# MCU_CORE.net
KiCad netlist of a schematic drawn in Altium Designer
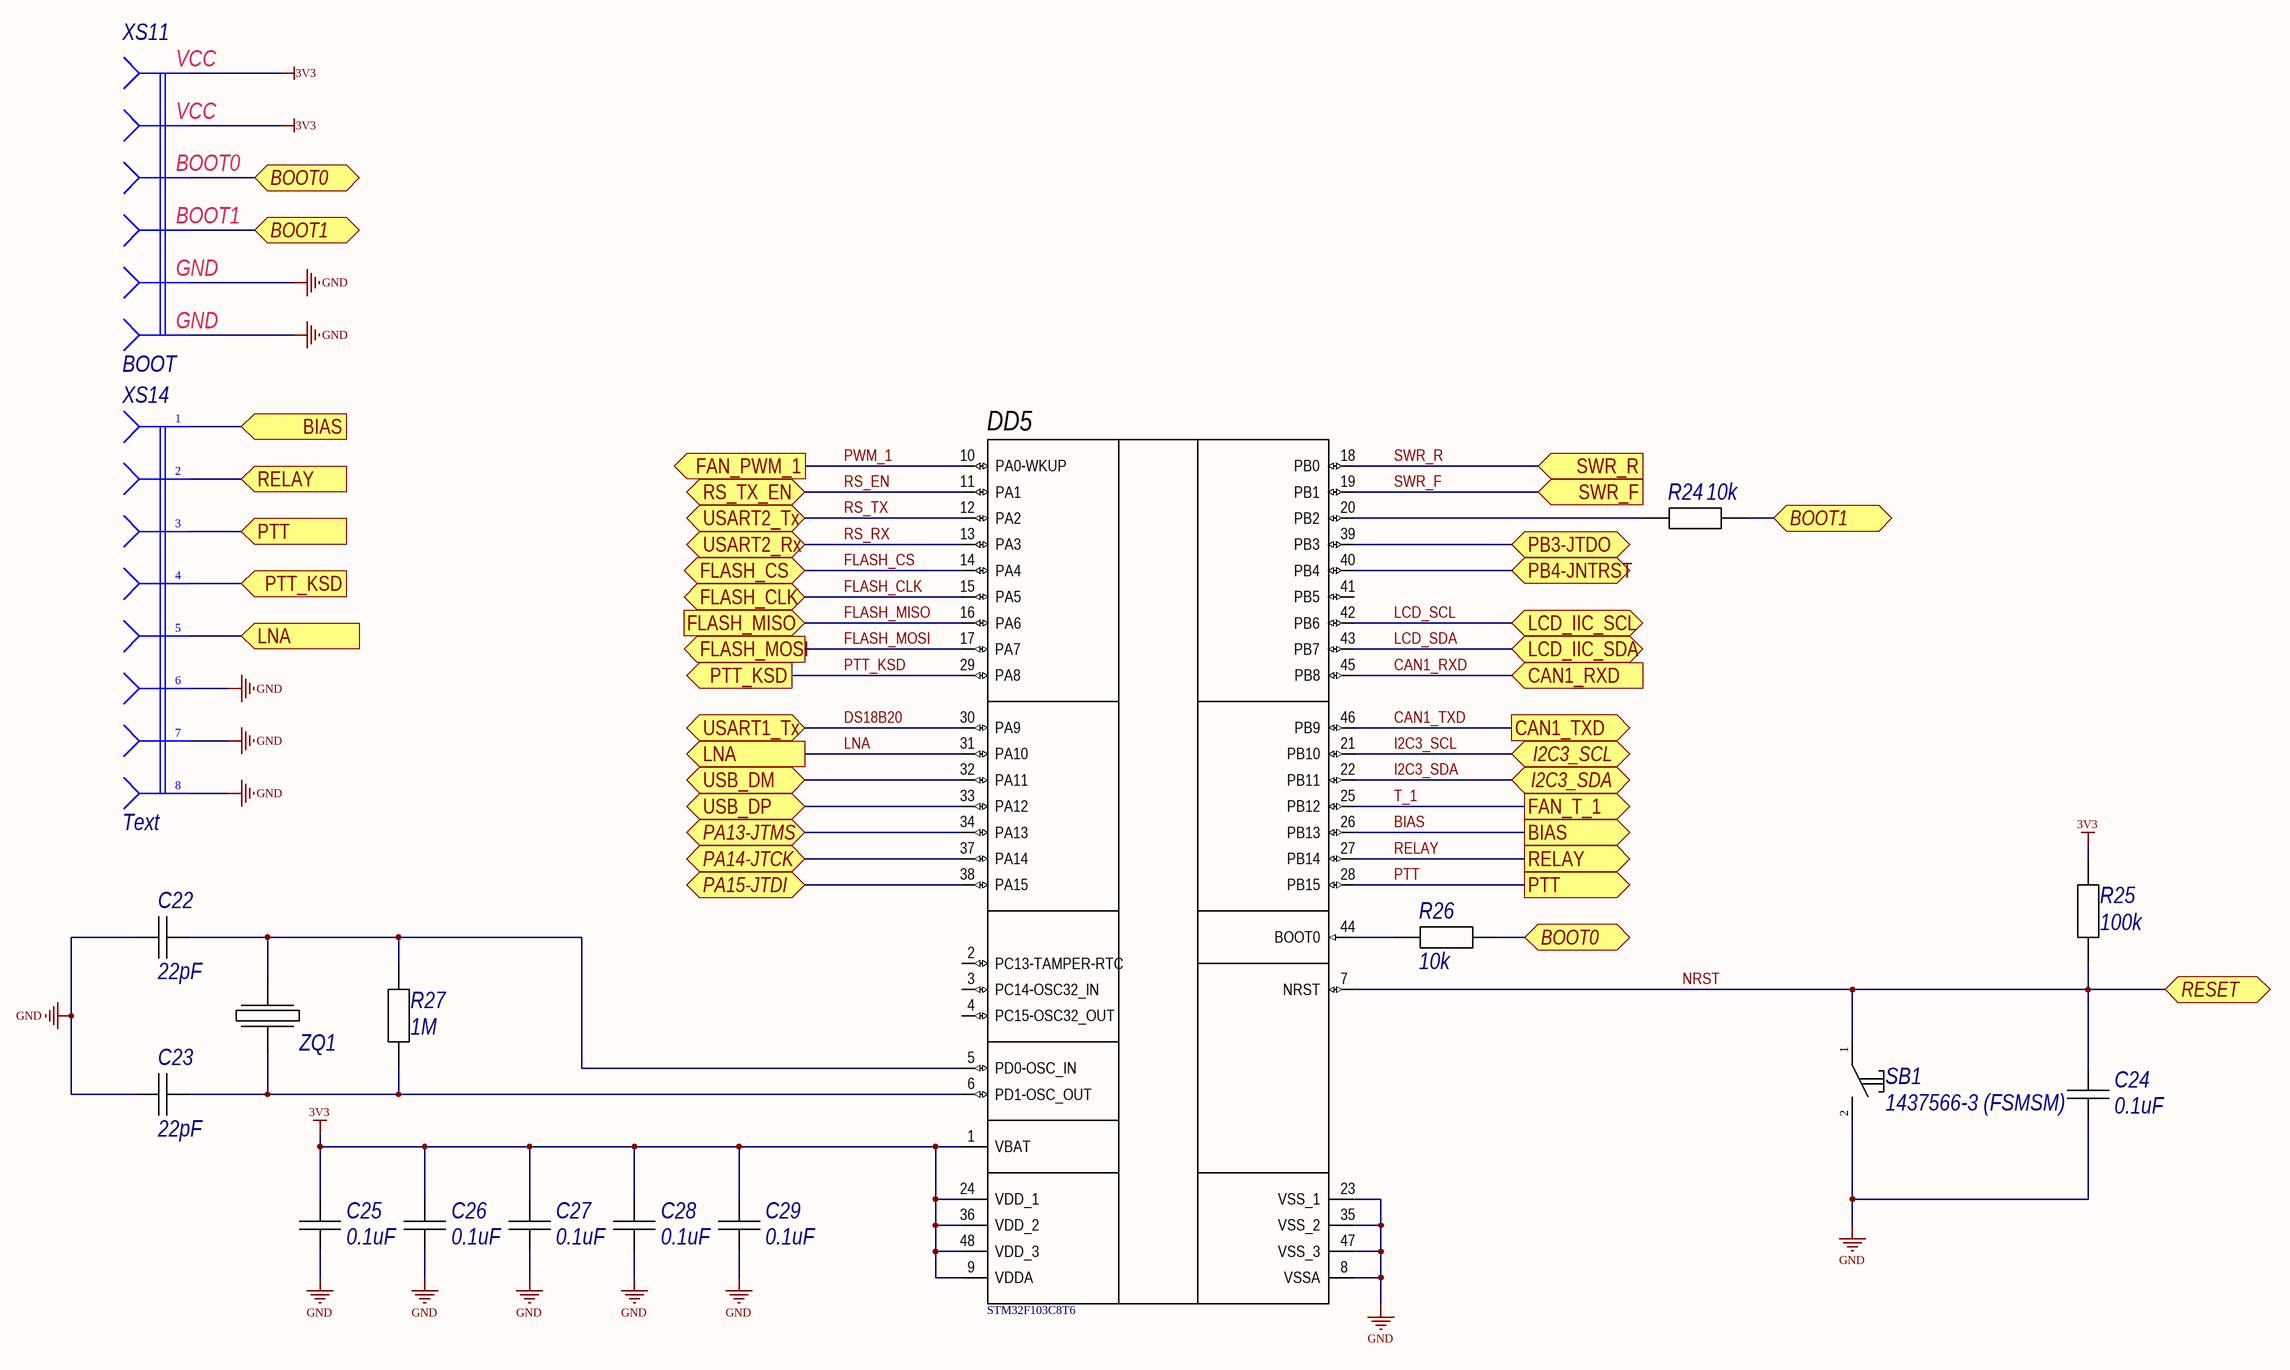
[diagram p0: MCU_CORE.SchDoc]

(export (version "E")
  (design (tool "Eeschema 10.0.6"))
  (components
    (comp (ref "C22")
      (value "22pF")
      (footprint "C0805C")
      (fields (field (name "PUBLISHER") "Andrew Danich"))
      (libsource (lib "PA_control_board") (part "CAP_0805"))
    )
    (comp (ref "C23")
      (value "22pF")
      (footprint "C0805C")
      (fields (field (name "PUBLISHER") "Andrew Danich"))
      (libsource (lib "PA_control_board") (part "CAP_0805"))
    )
    (comp (ref "C24")
      (value "0.1uF")
      (footprint "C0805C")
      (fields (field (name "PUBLISHER") "Andrew Danich"))
      (libsource (lib "PA_control_board") (part "CAP_0805"))
    )
    (comp (ref "C25")
      (value "0.1uF")
      (footprint "C0805C")
      (fields (field (name "PUBLISHER") "Andrew Danich"))
      (libsource (lib "PA_control_board") (part "CAP_0805"))
    )
    (comp (ref "C26")
      (value "0.1uF")
      (footprint "C0805C")
      (fields (field (name "PUBLISHER") "Andrew Danich"))
      (libsource (lib "PA_control_board") (part "CAP_0805"))
    )
    (comp (ref "C27")
      (value "0.1uF")
      (footprint "C0805C")
      (fields (field (name "PUBLISHER") "Andrew Danich"))
      (libsource (lib "PA_control_board") (part "CAP_0805"))
    )
    (comp (ref "C28")
      (value "0.1uF")
      (footprint "C0805C")
      (fields (field (name "PUBLISHER") "Andrew Danich"))
      (libsource (lib "PA_control_board") (part "CAP_0805"))
    )
    (comp (ref "C29")
      (value "0.1uF")
      (footprint "C0805C")
      (fields (field (name "PUBLISHER") "Andrew Danich"))
      (libsource (lib "PA_control_board") (part "CAP_0805"))
    )
    (comp (ref "DD5")
      (value "STM32F103C8T6")
      (footprint "STM-LQFP48_L")
      (libsource (lib "PA_control_board") (part "STM32F103C8T6"))
    )
    (comp (ref "R24")
      (value "10k")
      (footprint "C0805R")
      (fields (field (name "PUBLISHER") "Andrew Danich"))
      (libsource (lib "PA_control_board") (part "RES_0805"))
    )
    (comp (ref "R25")
      (value "100k")
      (footprint "C0805R")
      (fields (field (name "PUBLISHER") "Andrew Danich"))
      (libsource (lib "PA_control_board") (part "RES_0805"))
    )
    (comp (ref "R26")
      (value "10k")
      (footprint "C0805R")
      (fields (field (name "PUBLISHER") "Andrew Danich"))
      (libsource (lib "PA_control_board") (part "RES_0805"))
    )
    (comp (ref "R27")
      (value "1M")
      (footprint "C0805R")
      (fields (field (name "PUBLISHER") "Andrew Danich"))
      (libsource (lib "PA_control_board") (part "RES_0805"))
    )
    (comp (ref "SB1")
      (value "1437566-3 (FSMSM)")
      (footprint "1437566-3")
      (fields (field (name "PUBLISHER") "Andrew Danich"))
      (libsource (lib "PA_control_board") (part "BT-01x-01p"))
    )
    (comp (ref "XS11")
      (value "BOOT")
      (footprint "PLD2-3")
      (fields (field (name "PUBLISHER") "Andrew Danich"))
      (libsource (lib "PA_control_board") (part "CONNECT_BOOT"))
    )
    (comp (ref "XS14")
      (value "Text")
      (footprint "WF-8")
      (fields (field (name "PUBLISHER") "Andrew Danich"))
      (libsource (lib "PA_control_board") (part "Con-8-F"))
    )
    (comp (ref "ZQ1")
      (value "HC49SM")
      (footprint "HC49SM")
      (fields (field (name "PUBLISHER") "Andrew Danich"))
      (libsource (lib "PA_control_board") (part "HC49SM"))
    )
  )
  (nets
    (net (code "1") (name "/BIAS") (class "Default")
      (node (ref "DD5") (pin "26") (pinfunction "PB13_26") (pintype "bidirectional"))
      (node (ref "XS14") (pin "1") (pintype "passive"))
    )
    (net (code "2") (name "/BOOT0") (class "Default")
      (node (ref "R26") (pin "1") (pinfunction "1_1") (pintype "passive"))
      (node (ref "XS11") (pin "3") (pintype "passive"))
    )
    (net (code "3") (name "/BOOT1") (class "Default")
      (node (ref "R24") (pin "1") (pinfunction "1_1") (pintype "passive"))
      (node (ref "XS11") (pin "4") (pintype "passive"))
    )
    (net (code "4") (name "/CAN1_RXD") (class "Default")
      (node (ref "DD5") (pin "45") (pinfunction "PB8_45") (pintype "bidirectional"))
    )
    (net (code "5") (name "/CAN1_TXD") (class "Default")
      (node (ref "DD5") (pin "46") (pinfunction "PB9_46") (pintype "bidirectional"))
    )
    (net (code "6") (name "/DS18B20") (class "Default")
      (node (ref "DD5") (pin "30") (pinfunction "PA9_30") (pintype "bidirectional"))
    )
    (net (code "7") (name "/FLASH_CLK") (class "Default")
      (node (ref "DD5") (pin "15") (pinfunction "PA5_15") (pintype "bidirectional"))
    )
    (net (code "8") (name "/FLASH_CS") (class "Default")
      (node (ref "DD5") (pin "14") (pinfunction "PA4_14") (pintype "bidirectional"))
    )
    (net (code "9") (name "/FLASH_MISO") (class "Default")
      (node (ref "DD5") (pin "16") (pinfunction "PA6_16") (pintype "bidirectional"))
    )
    (net (code "10") (name "/FLASH_MOSI") (class "Default")
      (node (ref "DD5") (pin "17") (pinfunction "PA7_17") (pintype "bidirectional"))
    )
    (net (code "11") (name "/I2C3_SCL") (class "Default")
      (node (ref "DD5") (pin "21") (pinfunction "PB10_21") (pintype "bidirectional"))
    )
    (net (code "12") (name "/I2C3_SDA") (class "Default")
      (node (ref "DD5") (pin "22") (pinfunction "PB11_22") (pintype "bidirectional"))
    )
    (net (code "13") (name "/LCD_SCL") (class "Default")
      (node (ref "DD5") (pin "42") (pinfunction "PB6_42") (pintype "bidirectional"))
    )
    (net (code "14") (name "/LCD_SDA") (class "Default")
      (node (ref "DD5") (pin "43") (pinfunction "PB7_43") (pintype "bidirectional"))
    )
    (net (code "15") (name "/LNA") (class "Default")
      (node (ref "DD5") (pin "31") (pinfunction "PA10_31") (pintype "bidirectional"))
      (node (ref "XS14") (pin "5") (pintype "passive"))
    )
    (net (code "16") (name "/NRST") (class "Default")
      (node (ref "C24") (pin "2") (pinfunction "2_2") (pintype "passive"))
      (node (ref "DD5") (pin "7") (pinfunction "NRST_7") (pintype "bidirectional"))
      (node (ref "R25") (pin "2") (pinfunction "2_2") (pintype "passive"))
      (node (ref "SB1") (pin "1") (pintype "passive"))
    )
    (net (code "17") (name "/PA13-JTMS") (class "Default")
      (node (ref "DD5") (pin "34") (pinfunction "PA13_34") (pintype "bidirectional"))
    )
    (net (code "18") (name "/PA14-JTCK") (class "Default")
      (node (ref "DD5") (pin "37") (pinfunction "PA14_37") (pintype "bidirectional"))
    )
    (net (code "19") (name "/PA15-JTDI") (class "Default")
      (node (ref "DD5") (pin "38") (pinfunction "PA15_38") (pintype "bidirectional"))
    )
    (net (code "20") (name "/PB3-JTDO") (class "Default")
      (node (ref "DD5") (pin "39") (pinfunction "PB3_39") (pintype "bidirectional"))
    )
    (net (code "21") (name "/PB4-JNTRST") (class "Default")
      (node (ref "DD5") (pin "40") (pinfunction "PB4_40") (pintype "bidirectional"))
    )
    (net (code "22") (name "/PTT") (class "Default")
      (node (ref "DD5") (pin "28") (pinfunction "PB15_28") (pintype "bidirectional"))
      (node (ref "XS14") (pin "3") (pintype "passive"))
    )
    (net (code "23") (name "/PTT_KSD") (class "Default")
      (node (ref "DD5") (pin "29") (pinfunction "PA8_29") (pintype "bidirectional"))
      (node (ref "XS14") (pin "4") (pintype "passive"))
    )
    (net (code "24") (name "/PWM_1") (class "Default")
      (node (ref "DD5") (pin "10") (pinfunction "PA0-WKUP_10") (pintype "bidirectional"))
    )
    (net (code "25") (name "/RELAY") (class "Default")
      (node (ref "DD5") (pin "27") (pinfunction "PB14_27") (pintype "bidirectional"))
      (node (ref "XS14") (pin "2") (pintype "passive"))
    )
    (net (code "26") (name "/RS_EN") (class "Default")
      (node (ref "DD5") (pin "11") (pinfunction "PA1_11") (pintype "bidirectional"))
    )
    (net (code "27") (name "/RS_RX") (class "Default")
      (node (ref "DD5") (pin "13") (pinfunction "PA3_13") (pintype "bidirectional"))
    )
    (net (code "28") (name "/RS_TX") (class "Default")
      (node (ref "DD5") (pin "12") (pinfunction "PA2_12") (pintype "bidirectional"))
    )
    (net (code "29") (name "/SWR_F") (class "Default")
      (node (ref "DD5") (pin "19") (pinfunction "PB1_19") (pintype "bidirectional"))
    )
    (net (code "30") (name "/SWR_R") (class "Default")
      (node (ref "DD5") (pin "18") (pinfunction "PB0_18") (pintype "bidirectional"))
    )
    (net (code "31") (name "/T_1") (class "Default")
      (node (ref "DD5") (pin "25") (pinfunction "PB12_25") (pintype "bidirectional"))
    )
    (net (code "32") (name "/USB_DM") (class "Default")
      (node (ref "DD5") (pin "32") (pinfunction "PA11_32") (pintype "bidirectional"))
    )
    (net (code "33") (name "/USB_DP") (class "Default")
      (node (ref "DD5") (pin "33") (pinfunction "PA12_33") (pintype "bidirectional"))
    )
    (net (code "34") (name "3V3") (class "Default")
      (node (ref "C25") (pin "2") (pinfunction "2_2") (pintype "passive"))
      (node (ref "C26") (pin "2") (pinfunction "2_2") (pintype "passive"))
      (node (ref "C27") (pin "2") (pinfunction "2_2") (pintype "passive"))
      (node (ref "C28") (pin "2") (pinfunction "2_2") (pintype "passive"))
      (node (ref "C29") (pin "2") (pinfunction "2_2") (pintype "passive"))
      (node (ref "DD5") (pin "1") (pinfunction "VBAT_1") (pintype "power_in"))
      (node (ref "DD5") (pin "24") (pinfunction "VDD_1_24") (pintype "power_in"))
      (node (ref "DD5") (pin "36") (pinfunction "VDD_2_36") (pintype "power_in"))
      (node (ref "DD5") (pin "48") (pinfunction "VDD_3_48") (pintype "power_in"))
      (node (ref "DD5") (pin "9") (pinfunction "VDDA_9") (pintype "power_in"))
      (node (ref "R25") (pin "1") (pinfunction "1_1") (pintype "passive"))
      (node (ref "XS11") (pin "1") (pintype "passive"))
      (node (ref "XS11") (pin "2") (pintype "passive"))
    )
    (net (code "35") (name "GND") (class "Default")
      (node (ref "C22") (pin "1") (pinfunction "1_1") (pintype "passive"))
      (node (ref "C23") (pin "1") (pinfunction "1_1") (pintype "passive"))
      (node (ref "C24") (pin "1") (pinfunction "1_1") (pintype "passive"))
      (node (ref "C25") (pin "1") (pinfunction "1_1") (pintype "passive"))
      (node (ref "C26") (pin "1") (pinfunction "1_1") (pintype "passive"))
      (node (ref "C27") (pin "1") (pinfunction "1_1") (pintype "passive"))
      (node (ref "C28") (pin "1") (pinfunction "1_1") (pintype "passive"))
      (node (ref "C29") (pin "1") (pinfunction "1_1") (pintype "passive"))
      (node (ref "DD5") (pin "23") (pinfunction "VSS_1_23") (pintype "power_in"))
      (node (ref "DD5") (pin "35") (pinfunction "VSS_2_35") (pintype "power_in"))
      (node (ref "DD5") (pin "47") (pinfunction "VSS_3_47") (pintype "power_in"))
      (node (ref "DD5") (pin "8") (pinfunction "VSSA_8") (pintype "power_in"))
      (node (ref "SB1") (pin "2") (pintype "passive"))
      (node (ref "XS11") (pin "5") (pintype "passive"))
      (node (ref "XS11") (pin "6") (pintype "passive"))
      (node (ref "XS14") (pin "6") (pintype "passive"))
      (node (ref "XS14") (pin "7") (pintype "passive"))
      (node (ref "XS14") (pin "8") (pintype "passive"))
    )
    (net (code "36") (name "Net-(DD5-BOOT0)") (class "Default")
      (node (ref "DD5") (pin "44") (pinfunction "BOOT0_44") (pintype "input"))
      (node (ref "R26") (pin "2") (pinfunction "2_2") (pintype "passive"))
    )
    (net (code "37") (name "Net-(DD5-PB2)") (class "Default")
      (node (ref "DD5") (pin "20") (pinfunction "PB2_20") (pintype "bidirectional"))
      (node (ref "R24") (pin "2") (pinfunction "2_2") (pintype "passive"))
    )
    (net (code "38") (name "Net-(DD5-PD0-OSC_IN)") (class "Default")
      (node (ref "C22") (pin "2") (pinfunction "2_2") (pintype "passive"))
      (node (ref "DD5") (pin "5") (pinfunction "PD0-OSC_IN_5") (pintype "bidirectional"))
      (node (ref "R27") (pin "2") (pinfunction "2_2") (pintype "passive"))
      (node (ref "ZQ1") (pin "1") (pinfunction "1_1") (pintype "passive"))
    )
    (net (code "39") (name "Net-(DD5-PD1-OSC_OUT)") (class "Default")
      (node (ref "C23") (pin "2") (pinfunction "2_2") (pintype "passive"))
      (node (ref "DD5") (pin "6") (pinfunction "PD1-OSC_OUT_6") (pintype "bidirectional"))
      (node (ref "R27") (pin "1") (pinfunction "1_1") (pintype "passive"))
      (node (ref "ZQ1") (pin "2") (pinfunction "2_2") (pintype "passive"))
    )
    (net (code "40") (name "unconnected-(DD5-PB5-Pad41)") (class "Default")
      (node (ref "DD5") (pin "41") (pinfunction "PB5_41") (pintype "bidirectional"))
    )
    (net (code "41") (name "unconnected-(DD5-PC13-TAMPER-RTC-Pad2)") (class "Default")
      (node (ref "DD5") (pin "2") (pinfunction "PC13-TAMPER-RTC_2") (pintype "bidirectional"))
    )
    (net (code "42") (name "unconnected-(DD5-PC14-OSC32_IN-Pad3)") (class "Default")
      (node (ref "DD5") (pin "3") (pinfunction "PC14-OSC32_IN_3") (pintype "bidirectional"))
    )
    (net (code "43") (name "unconnected-(DD5-PC15-OSC32_OUT-Pad4)") (class "Default")
      (node (ref "DD5") (pin "4") (pinfunction "PC15-OSC32_OUT_4") (pintype "bidirectional"))
    )
  )
)
